# V01.net
KiCad netlist of a schematic drawn in Altium Designer
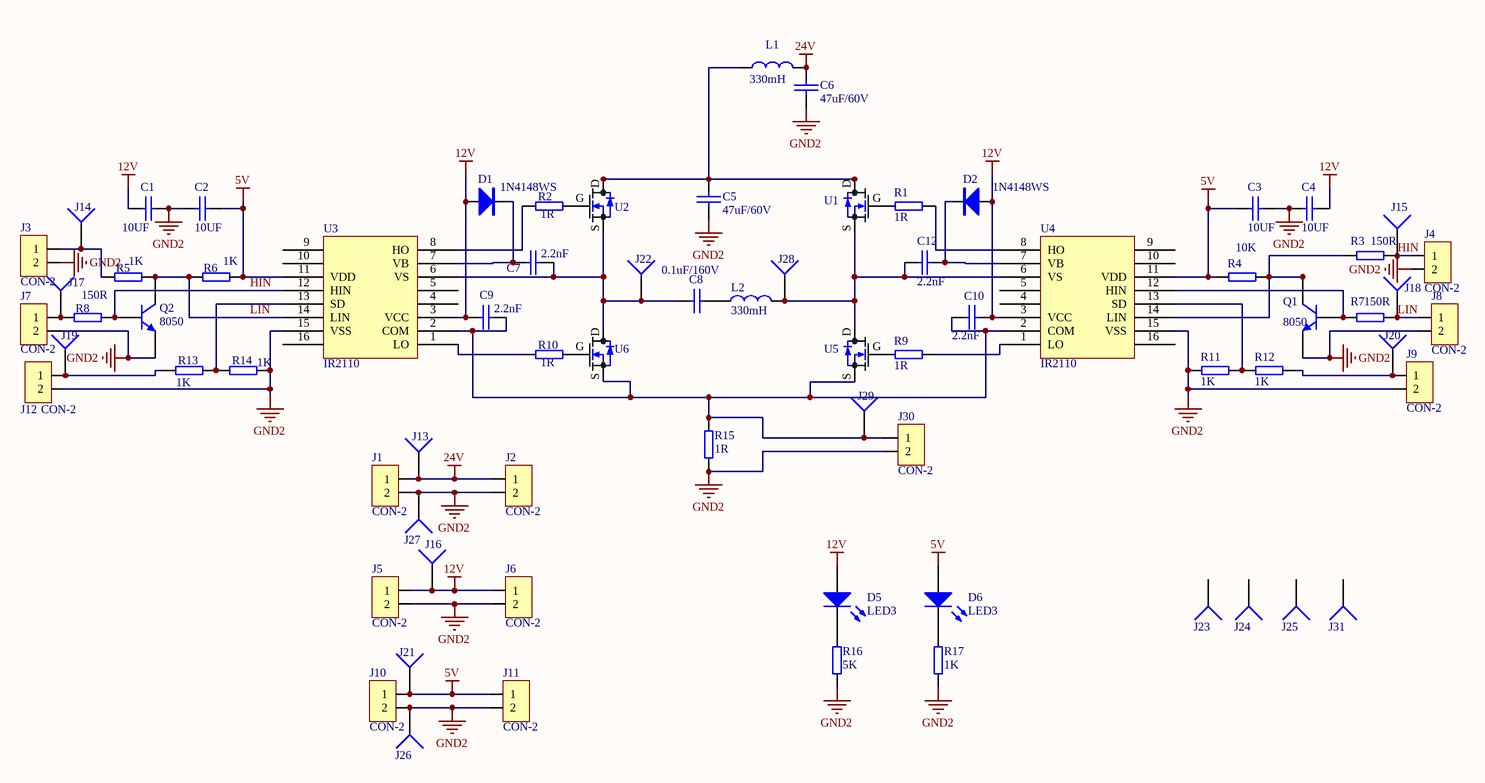
[diagram p0: 发送端V01.SchDoc]

(export (version "E")
  (design (tool "Eeschema 10.0.6"))
  (components
    (comp (ref "C1") (value "10UF") (footprint "1206_C") (libsource (lib "WegeV1") (part "CAP")))
    (comp (ref "C2") (value "10UF") (footprint "1206_C") (libsource (lib "WegeV1") (part "CAP")))
    (comp (ref "C3") (value "10UF") (footprint "1206_C") (libsource (lib "WegeV1") (part "CAP")))
    (comp (ref "C4") (value "10UF") (footprint "1206_C") (libsource (lib "WegeV1") (part "CAP")))
    (comp (ref "C5") (value "47uF/60V") (footprint "C3618") (libsource (lib "WegeV1") (part "CAP")))
    (comp (ref "C6") (value "47uF/60V") (footprint "C3618") (libsource (lib "WegeV1") (part "CAP")))
    (comp (ref "C7") (value "2.2nF") (footprint "1206_C") (libsource (lib "WegeV1") (part "CAP")))
    (comp (ref "C8") (value "0.1uF/160V") (footprint "DSMC82") (libsource (lib "WegeV1") (part "CAP")))
    (comp (ref "C9") (value "2.2nF") (footprint "1206_C") (libsource (lib "WegeV1") (part "CAP")))
    (comp (ref "C10") (value "2.2nF") (footprint "1206_C") (libsource (lib "WegeV1") (part "CAP")))
    (comp (ref "C12") (value "2.2nF") (footprint "1206_C") (libsource (lib "WegeV1") (part "CAP")))
    (comp (ref "D1")
      (value "1N4148WS")
      (footprint "SOD-123")
      (description "1N4148WS IN4148 0805 SOD323 丝印T4 贴片开关二极管")
      (libsource (lib "WegeV1") (part "1N4148"))
    )
    (comp (ref "D2")
      (value "1N4148WS")
      (footprint "SOD-123")
      (description "1N4148WS IN4148 0805 SOD323 丝印T4 贴片开关二极管")
      (libsource (lib "WegeV1") (part "1N4148"))
    )
    (comp (ref "D5")
      (value "LED3")
      (footprint "1206_R")
      (description "Typical BLUE SiC LED")
      (fields (field (name "PUBLISHER") "Altium Limited"))
      (libsource (lib "Miscellaneous Devices") (part "LED3"))
    )
    (comp (ref "D6")
      (value "LED3")
      (footprint "1206_R")
      (description "Typical BLUE SiC LED")
      (fields (field (name "PUBLISHER") "Altium Limited"))
      (libsource (lib "Miscellaneous Devices") (part "LED3"))
    )
    (comp (ref "J1") (value "CON-2") (footprint "F396P2-1") (libsource (lib "WegeV1") (part "CON-2")))
    (comp (ref "J2") (value "CON-2") (footprint "F396P2-1") (libsource (lib "") (part "CON-2_1")))
    (comp (ref "J3") (value "CON-2") (footprint "GPSPIN") (libsource (lib "WegeV1") (part "CON-2")))
    (comp (ref "J4") (value "CON-2") (footprint "GPSPIN") (libsource (lib "") (part "CON-2_1")))
    (comp (ref "J5") (value "CON-2") (footprint "F396P2-1") (libsource (lib "WegeV1") (part "CON-2")))
    (comp (ref "J6") (value "CON-2") (footprint "F396P2-1") (libsource (lib "") (part "CON-2_1")))
    (comp (ref "J7") (value "CON-2") (footprint "GPSPIN") (libsource (lib "WegeV1") (part "CON-2")))
    (comp (ref "J8") (value "CON-2") (footprint "GPSPIN") (libsource (lib "") (part "CON-2_1")))
    (comp (ref "J9") (value "CON-2") (footprint "HDR1X2") (libsource (lib "") (part "CON-2_1")))
    (comp (ref "J10") (value "CON-2") (footprint "F396P2-1") (libsource (lib "WegeV1") (part "CON-2")))
    (comp (ref "J11") (value "CON-2") (footprint "F396P2-1") (libsource (lib "") (part "CON-2_1")))
    (comp (ref "J12") (value "CON-2") (footprint "HDR1X2") (libsource (lib "WegeV1") (part "CON-2")))
    (comp (ref "J13")
      (value "Socket")
      (footprint "JET")
      (fields (field (name "PUBLISHER") "Altium Limited"))
      (libsource (lib "Miscellaneous Connectors") (part "Socket"))
    )
    (comp (ref "J14")
      (value "Socket")
      (footprint "JET")
      (fields (field (name "PUBLISHER") "Altium Limited"))
      (libsource (lib "Miscellaneous Connectors") (part "Socket"))
    )
    (comp (ref "J15")
      (value "Socket")
      (footprint "JET")
      (fields (field (name "PUBLISHER") "Altium Limited"))
      (libsource (lib "Miscellaneous Connectors") (part "Socket"))
    )
    (comp (ref "J16")
      (value "Socket")
      (footprint "JET")
      (fields (field (name "PUBLISHER") "Altium Limited"))
      (libsource (lib "Miscellaneous Connectors") (part "Socket"))
    )
    (comp (ref "J17")
      (value "Socket")
      (footprint "JET")
      (fields (field (name "PUBLISHER") "Altium Limited"))
      (libsource (lib "Miscellaneous Connectors") (part "Socket"))
    )
    (comp (ref "J18")
      (value "Socket")
      (footprint "JET")
      (fields (field (name "PUBLISHER") "Altium Limited"))
      (libsource (lib "Miscellaneous Connectors") (part "Socket"))
    )
    (comp (ref "J19")
      (value "Socket")
      (footprint "JET")
      (fields (field (name "PUBLISHER") "Altium Limited"))
      (libsource (lib "Miscellaneous Connectors") (part "Socket"))
    )
    (comp (ref "J20")
      (value "Socket")
      (footprint "JET")
      (fields (field (name "PUBLISHER") "Altium Limited"))
      (libsource (lib "Miscellaneous Connectors") (part "Socket"))
    )
    (comp (ref "J21")
      (value "Socket")
      (footprint "JET")
      (fields (field (name "PUBLISHER") "Altium Limited"))
      (libsource (lib "Miscellaneous Connectors") (part "Socket"))
    )
    (comp (ref "J22")
      (value "Socket")
      (footprint "JET")
      (fields (field (name "PUBLISHER") "Altium Limited"))
      (libsource (lib "Miscellaneous Connectors") (part "Socket"))
    )
    (comp (ref "J23")
      (value "Socket")
      (footprint "M3")
      (fields (field (name "PUBLISHER") "Altium Limited"))
      (libsource (lib "Miscellaneous Connectors") (part "Socket"))
    )
    (comp (ref "J24")
      (value "Socket")
      (footprint "M3")
      (fields (field (name "PUBLISHER") "Altium Limited"))
      (libsource (lib "Miscellaneous Connectors") (part "Socket"))
    )
    (comp (ref "J25")
      (value "Socket")
      (footprint "M3")
      (fields (field (name "PUBLISHER") "Altium Limited"))
      (libsource (lib "Miscellaneous Connectors") (part "Socket"))
    )
    (comp (ref "J26")
      (value "Socket")
      (footprint "JET")
      (fields (field (name "PUBLISHER") "Altium Limited"))
      (libsource (lib "Miscellaneous Connectors") (part "Socket"))
    )
    (comp (ref "J27")
      (value "Socket")
      (footprint "JET")
      (fields (field (name "PUBLISHER") "Altium Limited"))
      (libsource (lib "Miscellaneous Connectors") (part "Socket"))
    )
    (comp (ref "J28")
      (value "Socket")
      (footprint "JET")
      (fields (field (name "PUBLISHER") "Altium Limited"))
      (libsource (lib "Miscellaneous Connectors") (part "Socket"))
    )
    (comp (ref "J29")
      (value "Socket")
      (footprint "JET")
      (fields (field (name "PUBLISHER") "Altium Limited"))
      (libsource (lib "Miscellaneous Connectors") (part "Socket"))
    )
    (comp (ref "J30") (value "CON-2") (footprint "HDR1X2") (libsource (lib "") (part "CON-2_1")))
    (comp (ref "J31")
      (value "Socket")
      (footprint "M3")
      (fields (field (name "PUBLISHER") "Altium Limited"))
      (libsource (lib "Miscellaneous Connectors") (part "Socket"))
    )
    (comp (ref "L1")
      (value "330mH")
      (footprint "H3.3")
      (description "CD75--2.2mH 222M 贴片功率电感绕线功率电感 7*7.8*5mm")
      (libsource (lib "WegeV1") (part "INL"))
    )
    (comp (ref "L2")
      (value "330mH")
      (footprint "DSMC82")
      (description "CD75--2.2mH 222M 贴片功率电感绕线功率电感 7*7.8*5mm")
      (libsource (lib "WegeV1") (part "INL"))
    )
    (comp (ref "Q1")
      (value "8050")
      (footprint "SOT-23(SOT-23-3)")
      (description "三极管")
      (libsource (lib "Miscellaneous Devices LC") (part "SOT-23 2SC3356-T1B-A    S/YS档"))
    )
    (comp (ref "Q2")
      (value "8050")
      (footprint "SOT-23(SOT-23-3)")
      (description "三极管")
      (libsource (lib "Miscellaneous Devices LC") (part "SOT-23 2SC3356-T1B-A    S/YS档"))
    )
    (comp (ref "R1") (value "1R") (footprint "1206_R") (libsource (lib "WegeV1") (part "RES")))
    (comp (ref "R2") (value "1R") (footprint "1206_R") (libsource (lib "WegeV1") (part "RES")))
    (comp (ref "R3") (value "150R") (footprint "1206_R") (libsource (lib "WegeV1") (part "RES")))
    (comp (ref "R4") (value "10K") (footprint "1206_R") (libsource (lib "WegeV1") (part "RES")))
    (comp (ref "R5") (value "1K") (footprint "1206_R") (libsource (lib "WegeV1") (part "RES")))
    (comp (ref "R6") (value "1K") (footprint "1206_R") (libsource (lib "WegeV1") (part "RES")))
    (comp (ref "R7") (value "150R") (footprint "1206_R") (libsource (lib "WegeV1") (part "RES")))
    (comp (ref "R8") (value "150R") (footprint "1206_R") (libsource (lib "WegeV1") (part "RES")))
    (comp (ref "R9") (value "1R") (footprint "1206_R") (libsource (lib "WegeV1") (part "RES")))
    (comp (ref "R10") (value "1R") (footprint "1206_R") (libsource (lib "WegeV1") (part "RES")))
    (comp (ref "R11") (value "1K") (footprint "1206_R") (libsource (lib "WegeV1") (part "RES")))
    (comp (ref "R12") (value "1K") (footprint "1206_R") (libsource (lib "WegeV1") (part "RES")))
    (comp (ref "R13") (value "1K") (footprint "1206_R") (libsource (lib "WegeV1") (part "RES")))
    (comp (ref "R14") (value "1K") (footprint "1206_R") (libsource (lib "WegeV1") (part "RES")))
    (comp (ref "R15") (value "1R") (footprint "R10MR10MM1D5") (libsource (lib "WegeV1") (part "RES")))
    (comp (ref "R16") (value "5K") (footprint "1206_R") (libsource (lib "WegeV1") (part "RES")))
    (comp (ref "R17") (value "1K") (footprint "1206_R") (libsource (lib "WegeV1") (part "RES")))
    (comp (ref "U1") (value "NMOS") (footprint "TO-220") (libsource (lib "WegeV1") (part "NMOS")))
    (comp (ref "U2") (value "NMOS") (footprint "TO-220") (libsource (lib "WegeV1") (part "NMOS")))
    (comp (ref "U3")
      (value "IR2110")
      (footprint "SOIC-16_300mil")
      (libsource (lib "IC_temp") (part "IR2110"))
    )
    (comp (ref "U4") (value "IR2110") (footprint "SOIC-16_300mil") (libsource (lib "") (part "IR2110_1")))
    (comp (ref "U5") (value "NMOS") (footprint "TO-220") (libsource (lib "WegeV1") (part "NMOS")))
    (comp (ref "U6") (value "NMOS") (footprint "TO-220") (libsource (lib "WegeV1") (part "NMOS")))
  )
  (nets
    (net (code "1") (name "/HIN") (class "Default")
      (node (ref "J15") (pin "1") (pinfunction "1_1") (pintype "passive"))
      (node (ref "J4") (pin "1") (pinfunction "1_1") (pintype "passive"))
      (node (ref "Q2") (pin "1") (pinfunction "B_1") (pintype "passive"))
      (node (ref "R3") (pin "1") (pinfunction "1_1") (pintype "passive"))
      (node (ref "R8") (pin "2") (pinfunction "2_2") (pintype "passive"))
      (node (ref "U3") (pin "12") (pinfunction "HIN_12") (pintype "passive"))
    )
    (net (code "2") (name "/LIN") (class "Default")
      (node (ref "J18") (pin "1") (pinfunction "1_1") (pintype "passive"))
      (node (ref "J8") (pin "1") (pinfunction "1_1") (pintype "passive"))
      (node (ref "Q2") (pin "3") (pinfunction "C_3") (pintype "passive"))
      (node (ref "R5") (pin "2") (pinfunction "2_2") (pintype "passive"))
      (node (ref "R6") (pin "1") (pinfunction "1_1") (pintype "passive"))
      (node (ref "R7") (pin "1") (pinfunction "1_1") (pintype "passive"))
      (node (ref "U3") (pin "14") (pinfunction "LIN_14") (pintype "passive"))
    )
    (net (code "3") (name "5V") (class "Default")
      (node (ref "C2") (pin "1") (pinfunction "1_1") (pintype "passive"))
      (node (ref "C3") (pin "1") (pinfunction "1_1") (pintype "passive"))
      (node (ref "D6") (pin "1") (pinfunction "A_1") (pintype "passive"))
      (node (ref "J10") (pin "1") (pinfunction "1_1") (pintype "passive"))
      (node (ref "J11") (pin "1") (pinfunction "1_1") (pintype "passive"))
      (node (ref "J21") (pin "1") (pinfunction "1_1") (pintype "passive"))
      (node (ref "R4") (pin "2") (pinfunction "2_2") (pintype "passive"))
      (node (ref "R6") (pin "2") (pinfunction "2_2") (pintype "passive"))
      (node (ref "U3") (pin "11") (pinfunction "VDD_11") (pintype "passive"))
      (node (ref "U4") (pin "11") (pinfunction "VDD_11") (pintype "passive"))
    )
    (net (code "4") (name "12V") (class "Default")
      (node (ref "C1") (pin "2") (pinfunction "2_2") (pintype "passive"))
      (node (ref "C10") (pin "2") (pinfunction "2_2") (pintype "passive"))
      (node (ref "C4") (pin "2") (pinfunction "2_2") (pintype "passive"))
      (node (ref "C9") (pin "2") (pinfunction "2_2") (pintype "passive"))
      (node (ref "D1") (pin "1") (pinfunction "A_1") (pintype "passive"))
      (node (ref "D2") (pin "1") (pinfunction "A_1") (pintype "passive"))
      (node (ref "D5") (pin "1") (pinfunction "A_1") (pintype "passive"))
      (node (ref "J16") (pin "1") (pinfunction "1_1") (pintype "passive"))
      (node (ref "J5") (pin "1") (pinfunction "1_1") (pintype "passive"))
      (node (ref "J6") (pin "1") (pinfunction "1_1") (pintype "passive"))
      (node (ref "U3") (pin "3") (pinfunction "VCC_3") (pintype "passive"))
      (node (ref "U4") (pin "3") (pinfunction "VCC_3") (pintype "passive"))
    )
    (net (code "5") (name "24V") (class "Default")
      (node (ref "C6") (pin "1") (pinfunction "1_1") (pintype "passive"))
      (node (ref "J1") (pin "1") (pinfunction "1_1") (pintype "passive"))
      (node (ref "J13") (pin "1") (pinfunction "1_1") (pintype "passive"))
      (node (ref "J2") (pin "1") (pinfunction "1_1") (pintype "passive"))
      (node (ref "L1") (pin "1") (pinfunction "1_1") (pintype "passive"))
    )
    (net (code "6") (name "GND2") (class "Default")
      (node (ref "C1") (pin "1") (pinfunction "1_1") (pintype "passive"))
      (node (ref "C2") (pin "2") (pinfunction "2_2") (pintype "passive"))
      (node (ref "C3") (pin "2") (pinfunction "2_2") (pintype "passive"))
      (node (ref "C4") (pin "1") (pinfunction "1_1") (pintype "passive"))
      (node (ref "C5") (pin "2") (pinfunction "2_2") (pintype "passive"))
      (node (ref "C6") (pin "2") (pinfunction "2_2") (pintype "passive"))
      (node (ref "J1") (pin "2") (pinfunction "2_2") (pintype "passive"))
      (node (ref "J10") (pin "2") (pinfunction "2_2") (pintype "passive"))
      (node (ref "J11") (pin "2") (pinfunction "2_2") (pintype "passive"))
      (node (ref "J12") (pin "2") (pinfunction "2_2") (pintype "passive"))
      (node (ref "J2") (pin "2") (pinfunction "2_2") (pintype "passive"))
      (node (ref "J26") (pin "1") (pinfunction "1_1") (pintype "passive"))
      (node (ref "J27") (pin "1") (pinfunction "1_1") (pintype "passive"))
      (node (ref "J3") (pin "2") (pinfunction "2_2") (pintype "passive"))
      (node (ref "J30") (pin "2") (pinfunction "2_2") (pintype "passive"))
      (node (ref "J4") (pin "2") (pinfunction "2_2") (pintype "passive"))
      (node (ref "J5") (pin "2") (pinfunction "2_2") (pintype "passive"))
      (node (ref "J6") (pin "2") (pinfunction "2_2") (pintype "passive"))
      (node (ref "J7") (pin "2") (pinfunction "2_2") (pintype "passive"))
      (node (ref "J8") (pin "2") (pinfunction "2_2") (pintype "passive"))
      (node (ref "J9") (pin "2") (pinfunction "2_2") (pintype "passive"))
      (node (ref "Q1") (pin "2") (pinfunction "E_2") (pintype "passive"))
      (node (ref "Q2") (pin "2") (pinfunction "E_2") (pintype "passive"))
      (node (ref "R11") (pin "2") (pinfunction "2_2") (pintype "passive"))
      (node (ref "R14") (pin "2") (pinfunction "2_2") (pintype "passive"))
      (node (ref "R15") (pin "1") (pinfunction "1_1") (pintype "passive"))
      (node (ref "R16") (pin "1") (pinfunction "1_1") (pintype "passive"))
      (node (ref "R17") (pin "1") (pinfunction "1_1") (pintype "passive"))
      (node (ref "U3") (pin "15") (pinfunction "VSS_15") (pintype "passive"))
      (node (ref "U4") (pin "15") (pinfunction "VSS_15") (pintype "passive"))
    )
    (net (code "7") (name "Net-(C5-Pad1)") (class "Default")
      (node (ref "C5") (pin "1") (pinfunction "1_1") (pintype "passive"))
      (node (ref "L1") (pin "2") (pinfunction "2_2") (pintype "passive"))
      (node (ref "U1") (pin "D") (pinfunction "D_D") (pintype "passive"))
      (node (ref "U2") (pin "D") (pinfunction "D_D") (pintype "passive"))
    )
    (net (code "8") (name "Net-(C8-Pad2)") (class "Default")
      (node (ref "C8") (pin "2") (pinfunction "2_2") (pintype "passive"))
      (node (ref "L2") (pin "2") (pinfunction "2_2") (pintype "passive"))
    )
    (net (code "9") (name "Net-(D1-K)") (class "Default")
      (node (ref "C7") (pin "2") (pinfunction "2_2") (pintype "passive"))
      (node (ref "D1") (pin "2") (pinfunction "K_2") (pintype "passive"))
      (node (ref "U3") (pin "7") (pinfunction "VB_7") (pintype "passive"))
    )
    (net (code "10") (name "Net-(D2-K)") (class "Default")
      (node (ref "C12") (pin "2") (pinfunction "2_2") (pintype "passive"))
      (node (ref "D2") (pin "2") (pinfunction "K_2") (pintype "passive"))
      (node (ref "U4") (pin "7") (pinfunction "VB_7") (pintype "passive"))
    )
    (net (code "11") (name "Net-(D5-K)") (class "Default")
      (node (ref "D5") (pin "2") (pinfunction "K_2") (pintype "passive"))
      (node (ref "R16") (pin "2") (pinfunction "2_2") (pintype "passive"))
    )
    (net (code "12") (name "Net-(D6-K)") (class "Default")
      (node (ref "D6") (pin "2") (pinfunction "K_2") (pintype "passive"))
      (node (ref "R17") (pin "2") (pinfunction "2_2") (pintype "passive"))
    )
    (net (code "13") (name "Net-(J12-Pad1)") (class "Default")
      (node (ref "J12") (pin "1") (pinfunction "1_1") (pintype "passive"))
      (node (ref "J19") (pin "1") (pinfunction "1_1") (pintype "passive"))
      (node (ref "R13") (pin "1") (pinfunction "1_1") (pintype "passive"))
    )
    (net (code "14") (name "Net-(J14-Pad1)") (class "Default")
      (node (ref "J14") (pin "1") (pinfunction "1_1") (pintype "passive"))
      (node (ref "J3") (pin "1") (pinfunction "1_1") (pintype "passive"))
      (node (ref "R5") (pin "1") (pinfunction "1_1") (pintype "passive"))
    )
    (net (code "15") (name "Net-(J17-Pad1)") (class "Default")
      (node (ref "J17") (pin "1") (pinfunction "1_1") (pintype "passive"))
      (node (ref "J7") (pin "1") (pinfunction "1_1") (pintype "passive"))
      (node (ref "R8") (pin "1") (pinfunction "1_1") (pintype "passive"))
    )
    (net (code "16") (name "Net-(J20-Pad1)") (class "Default")
      (node (ref "J20") (pin "1") (pinfunction "1_1") (pintype "passive"))
      (node (ref "J9") (pin "1") (pinfunction "1_1") (pintype "passive"))
      (node (ref "R12") (pin "1") (pinfunction "1_1") (pintype "passive"))
    )
    (net (code "17") (name "Net-(Q1-B)") (class "Default")
      (node (ref "Q1") (pin "1") (pinfunction "B_1") (pintype "passive"))
      (node (ref "R7") (pin "2") (pinfunction "2_2") (pintype "passive"))
      (node (ref "U4") (pin "12") (pinfunction "HIN_12") (pintype "passive"))
    )
    (net (code "18") (name "Net-(Q1-C)") (class "Default")
      (node (ref "Q1") (pin "3") (pinfunction "C_3") (pintype "passive"))
      (node (ref "R3") (pin "2") (pinfunction "2_2") (pintype "passive"))
      (node (ref "R4") (pin "1") (pinfunction "1_1") (pintype "passive"))
      (node (ref "U4") (pin "14") (pinfunction "LIN_14") (pintype "passive"))
    )
    (net (code "19") (name "Net-(R1-Pad2)") (class "Default")
      (node (ref "R1") (pin "2") (pinfunction "2_2") (pintype "passive"))
      (node (ref "U1") (pin "G") (pinfunction "G_G") (pintype "passive"))
    )
    (net (code "20") (name "Net-(R2-Pad2)") (class "Default")
      (node (ref "R2") (pin "2") (pinfunction "2_2") (pintype "passive"))
      (node (ref "U2") (pin "G") (pinfunction "G_G") (pintype "passive"))
    )
    (net (code "21") (name "Net-(R9-Pad2)") (class "Default")
      (node (ref "R9") (pin "2") (pinfunction "2_2") (pintype "passive"))
      (node (ref "U5") (pin "G") (pinfunction "G_G") (pintype "passive"))
    )
    (net (code "22") (name "Net-(R10-Pad2)") (class "Default")
      (node (ref "R10") (pin "2") (pinfunction "2_2") (pintype "passive"))
      (node (ref "U6") (pin "G") (pinfunction "G_G") (pintype "passive"))
    )
    (net (code "23") (name "Net-(U3-COM)") (class "Default")
      (node (ref "C10") (pin "1") (pinfunction "1_1") (pintype "passive"))
      (node (ref "C9") (pin "1") (pinfunction "1_1") (pintype "passive"))
      (node (ref "J29") (pin "1") (pinfunction "1_1") (pintype "passive"))
      (node (ref "J30") (pin "1") (pinfunction "1_1") (pintype "passive"))
      (node (ref "R15") (pin "2") (pinfunction "2_2") (pintype "passive"))
      (node (ref "U3") (pin "2") (pinfunction "COM_2") (pintype "passive"))
      (node (ref "U4") (pin "2") (pinfunction "COM_2") (pintype "passive"))
      (node (ref "U5") (pin "S") (pinfunction "S_S") (pintype "passive"))
      (node (ref "U6") (pin "S") (pinfunction "S_S") (pintype "passive"))
    )
    (net (code "24") (name "Net-(U3-HO)") (class "Default")
      (node (ref "R2") (pin "1") (pinfunction "1_1") (pintype "passive"))
      (node (ref "U3") (pin "8") (pinfunction "HO_8") (pintype "passive"))
    )
    (net (code "25") (name "Net-(U3-LO)") (class "Default")
      (node (ref "R10") (pin "1") (pinfunction "1_1") (pintype "passive"))
      (node (ref "U3") (pin "1") (pinfunction "LO_1") (pintype "passive"))
    )
    (net (code "26") (name "Net-(U3-SD)") (class "Default")
      (node (ref "R13") (pin "2") (pinfunction "2_2") (pintype "passive"))
      (node (ref "R14") (pin "1") (pinfunction "1_1") (pintype "passive"))
      (node (ref "U3") (pin "13") (pinfunction "SD_13") (pintype "passive"))
    )
    (net (code "27") (name "Net-(U3-VS)") (class "Default")
      (node (ref "C7") (pin "1") (pinfunction "1_1") (pintype "passive"))
      (node (ref "C8") (pin "1") (pinfunction "1_1") (pintype "passive"))
      (node (ref "J22") (pin "1") (pinfunction "1_1") (pintype "passive"))
      (node (ref "U2") (pin "S") (pinfunction "S_S") (pintype "passive"))
      (node (ref "U3") (pin "6") (pinfunction "VS_6") (pintype "passive"))
      (node (ref "U6") (pin "D") (pinfunction "D_D") (pintype "passive"))
    )
    (net (code "28") (name "Net-(U4-HO)") (class "Default")
      (node (ref "R1") (pin "1") (pinfunction "1_1") (pintype "passive"))
      (node (ref "U4") (pin "8") (pinfunction "HO_8") (pintype "passive"))
    )
    (net (code "29") (name "Net-(U4-LO)") (class "Default")
      (node (ref "R9") (pin "1") (pinfunction "1_1") (pintype "passive"))
      (node (ref "U4") (pin "1") (pinfunction "LO_1") (pintype "passive"))
    )
    (net (code "30") (name "Net-(U4-SD)") (class "Default")
      (node (ref "R11") (pin "1") (pinfunction "1_1") (pintype "passive"))
      (node (ref "R12") (pin "2") (pinfunction "2_2") (pintype "passive"))
      (node (ref "U4") (pin "13") (pinfunction "SD_13") (pintype "passive"))
    )
    (net (code "31") (name "Net-(U4-VS)") (class "Default")
      (node (ref "C12") (pin "1") (pinfunction "1_1") (pintype "passive"))
      (node (ref "J28") (pin "1") (pinfunction "1_1") (pintype "passive"))
      (node (ref "L2") (pin "1") (pinfunction "1_1") (pintype "passive"))
      (node (ref "U1") (pin "S") (pinfunction "S_S") (pintype "passive"))
      (node (ref "U4") (pin "6") (pinfunction "VS_6") (pintype "passive"))
      (node (ref "U5") (pin "D") (pinfunction "D_D") (pintype "passive"))
    )
    (net (code "32") (name "unconnected-(J23-Pad1)") (class "Default")
      (node (ref "J23") (pin "1") (pinfunction "1_1") (pintype "passive"))
    )
    (net (code "33") (name "unconnected-(J24-Pad1)") (class "Default")
      (node (ref "J24") (pin "1") (pinfunction "1_1") (pintype "passive"))
    )
    (net (code "34") (name "unconnected-(J25-Pad1)") (class "Default")
      (node (ref "J25") (pin "1") (pinfunction "1_1") (pintype "passive"))
    )
    (net (code "35") (name "unconnected-(J31-Pad1)") (class "Default")
      (node (ref "J31") (pin "1") (pinfunction "1_1") (pintype "passive"))
    )
    (net (code "36") (name "unconnected-(U3-Pad4)") (class "Default")
      (node (ref "U3") (pin "4") (pintype "passive"))
    )
    (net (code "37") (name "unconnected-(U3-Pad5)") (class "Default")
      (node (ref "U3") (pin "5") (pintype "passive"))
    )
    (net (code "38") (name "unconnected-(U3-Pad9)") (class "Default")
      (node (ref "U3") (pin "9") (pintype "passive"))
    )
    (net (code "39") (name "unconnected-(U3-Pad10)") (class "Default")
      (node (ref "U3") (pin "10") (pintype "passive"))
    )
    (net (code "40") (name "unconnected-(U3-Pad16)") (class "Default")
      (node (ref "U3") (pin "16") (pintype "passive"))
    )
    (net (code "41") (name "unconnected-(U4-Pad4)") (class "Default")
      (node (ref "U4") (pin "4") (pintype "passive"))
    )
    (net (code "42") (name "unconnected-(U4-Pad5)") (class "Default")
      (node (ref "U4") (pin "5") (pintype "passive"))
    )
    (net (code "43") (name "unconnected-(U4-Pad9)") (class "Default")
      (node (ref "U4") (pin "9") (pintype "passive"))
    )
    (net (code "44") (name "unconnected-(U4-Pad10)") (class "Default")
      (node (ref "U4") (pin "10") (pintype "passive"))
    )
    (net (code "45") (name "unconnected-(U4-Pad16)") (class "Default")
      (node (ref "U4") (pin "16") (pintype "passive"))
    )
  )
)
